# Slave1.net
KiCad netlist of a schematic drawn in Altium Designer
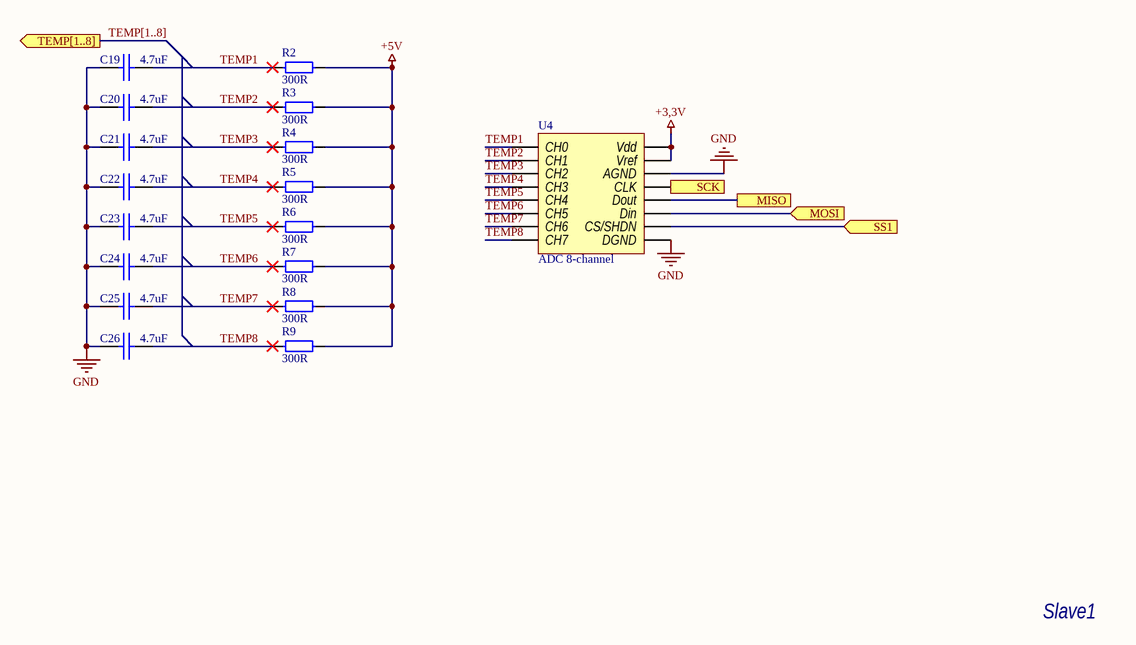
[diagram p0: Slave1.SchDoc]

(export (version "E")
  (design (tool "Eeschema 10.0.6"))
  (components
    (comp (ref "C19")
      (value "4.7uF")
      (footprint "0603 Capicator")
      (description "4.7uF X5R 25V 10% 0603")
      (fields
        (field (name "MANUFACTURER") "Murata Manufacturing")
        (field (name "PART NUMBER") "GRM188R61E475KE11D")
      )
      (libsource (lib "БУС") (part "Cap 4.7uF (0603)"))
    )
    (comp (ref "C20")
      (value "4.7uF")
      (footprint "0603 Capicator")
      (description "4.7uF X5R 25V 10% 0603")
      (fields
        (field (name "MANUFACTURER") "Murata Manufacturing")
        (field (name "PART NUMBER") "GRM188R61E475KE11D")
      )
      (libsource (lib "БУС") (part "Cap 4.7uF (0603)"))
    )
    (comp (ref "C21")
      (value "4.7uF")
      (footprint "0603 Capicator")
      (description "4.7uF X5R 25V 10% 0603")
      (fields
        (field (name "MANUFACTURER") "Murata Manufacturing")
        (field (name "PART NUMBER") "GRM188R61E475KE11D")
      )
      (libsource (lib "БУС") (part "Cap 4.7uF (0603)"))
    )
    (comp (ref "C22")
      (value "4.7uF")
      (footprint "0603 Capicator")
      (description "4.7uF X5R 25V 10% 0603")
      (fields
        (field (name "MANUFACTURER") "Murata Manufacturing")
        (field (name "PART NUMBER") "GRM188R61E475KE11D")
      )
      (libsource (lib "БУС") (part "Cap 4.7uF (0603)"))
    )
    (comp (ref "C23")
      (value "4.7uF")
      (footprint "0603 Capicator")
      (description "4.7uF X5R 25V 10% 0603")
      (fields
        (field (name "MANUFACTURER") "Murata Manufacturing")
        (field (name "PART NUMBER") "GRM188R61E475KE11D")
      )
      (libsource (lib "БУС") (part "Cap 4.7uF (0603)"))
    )
    (comp (ref "C24")
      (value "4.7uF")
      (footprint "0603 Capicator")
      (description "4.7uF X5R 25V 10% 0603")
      (fields
        (field (name "MANUFACTURER") "Murata Manufacturing")
        (field (name "PART NUMBER") "GRM188R61E475KE11D")
      )
      (libsource (lib "БУС") (part "Cap 4.7uF (0603)"))
    )
    (comp (ref "C25")
      (value "4.7uF")
      (footprint "0603 Capicator")
      (description "4.7uF X5R 25V 10% 0603")
      (fields
        (field (name "MANUFACTURER") "Murata Manufacturing")
        (field (name "PART NUMBER") "GRM188R61E475KE11D")
      )
      (libsource (lib "БУС") (part "Cap 4.7uF (0603)"))
    )
    (comp (ref "C26")
      (value "4.7uF")
      (footprint "0603 Capicator")
      (description "4.7uF X5R 25V 10% 0603")
      (fields
        (field (name "MANUFACTURER") "Murata Manufacturing")
        (field (name "PART NUMBER") "GRM188R61E475KE11D")
      )
      (libsource (lib "БУС") (part "Cap 4.7uF (0603)"))
    )
    (comp (ref "R2")
      (value "300R")
      (footprint "0603 Resistor")
      (description "0.1W 0603 300R, 1%")
      (fields (field (name "PART NUMBER") "RC0603FR-07360RL") (field (name "MANUFACTURER") "Taiwan"))
      (libsource (lib "БУС") (part "Res 300R (0603)"))
    )
    (comp (ref "R3")
      (value "300R")
      (footprint "0603 Resistor")
      (description "0.1W 0603 300R, 1%")
      (fields (field (name "PART NUMBER") "RC0603FR-07360RL") (field (name "MANUFACTURER") "Taiwan"))
      (libsource (lib "БУС") (part "Res 300R (0603)"))
    )
    (comp (ref "R4")
      (value "300R")
      (footprint "0603 Resistor")
      (description "0.1W 0603 300R, 1%")
      (fields (field (name "PART NUMBER") "RC0603FR-07360RL") (field (name "MANUFACTURER") "Taiwan"))
      (libsource (lib "БУС") (part "Res 300R (0603)"))
    )
    (comp (ref "R5")
      (value "300R")
      (footprint "0603 Resistor")
      (description "0.1W 0603 300R, 1%")
      (fields (field (name "PART NUMBER") "RC0603FR-07360RL") (field (name "MANUFACTURER") "Taiwan"))
      (libsource (lib "БУС") (part "Res 300R (0603)"))
    )
    (comp (ref "R6")
      (value "300R")
      (footprint "0603 Resistor")
      (description "0.1W 0603 300R, 1%")
      (fields (field (name "PART NUMBER") "RC0603FR-07360RL") (field (name "MANUFACTURER") "Taiwan"))
      (libsource (lib "БУС") (part "Res 300R (0603)"))
    )
    (comp (ref "R7")
      (value "300R")
      (footprint "0603 Resistor")
      (description "0.1W 0603 300R, 1%")
      (fields (field (name "PART NUMBER") "RC0603FR-07360RL") (field (name "MANUFACTURER") "Taiwan"))
      (libsource (lib "БУС") (part "Res 300R (0603)"))
    )
    (comp (ref "R8")
      (value "300R")
      (footprint "0603 Resistor")
      (description "0.1W 0603 300R, 1%")
      (fields (field (name "PART NUMBER") "RC0603FR-07360RL") (field (name "MANUFACTURER") "Taiwan"))
      (libsource (lib "БУС") (part "Res 300R (0603)"))
    )
    (comp (ref "R9")
      (value "300R")
      (footprint "0603 Resistor")
      (description "0.1W 0603 300R, 1%")
      (fields (field (name "PART NUMBER") "RC0603FR-07360RL") (field (name "MANUFACTURER") "Taiwan"))
      (libsource (lib "БУС") (part "Res 300R (0603)"))
    )
    (comp (ref "U4")
      (value "ADC 8-channel")
      (footprint "SOIC-16")
      (description "A/D converter with SPI serial interface")
      (fields (field (name "MANUFACTURER") "Microchip") (field (name "PART NUMBER") "MCP3008-I/SL"))
      (libsource (lib "БУС") (part "MCP3008-I/SL"))
    )
  )
  (nets
    (net (code "1") (name "+3,3V") (class "Default")
      (node (ref "U4") (pin "15") (pinfunction "Vref_15") (pintype "passive"))
      (node (ref "U4") (pin "16") (pinfunction "Vdd_16") (pintype "passive"))
    )
    (net (code "2") (name "+5V") (class "Default")
      (node (ref "R2") (pin "2") (pinfunction "2_2") (pintype "passive"))
      (node (ref "R3") (pin "2") (pinfunction "2_2") (pintype "passive"))
      (node (ref "R4") (pin "2") (pinfunction "2_2") (pintype "passive"))
      (node (ref "R5") (pin "2") (pinfunction "2_2") (pintype "passive"))
      (node (ref "R6") (pin "2") (pinfunction "2_2") (pintype "passive"))
      (node (ref "R7") (pin "2") (pinfunction "2_2") (pintype "passive"))
      (node (ref "R8") (pin "2") (pinfunction "2_2") (pintype "passive"))
      (node (ref "R9") (pin "2") (pinfunction "2_2") (pintype "passive"))
    )
    (net (code "3") (name "/MISO") (class "Default")
      (node (ref "U4") (pin "12") (pinfunction "Dout_12") (pintype "passive"))
    )
    (net (code "4") (name "/MOSI") (class "Default")
      (node (ref "U4") (pin "11") (pinfunction "Din_11") (pintype "passive"))
    )
    (net (code "5") (name "/SCK") (class "Default")
      (node (ref "U4") (pin "13") (pinfunction "CLK_13") (pintype "passive"))
    )
    (net (code "6") (name "/SS1") (class "Default")
      (node (ref "U4") (pin "10") (pinfunction "CS/SHDN_10") (pintype "passive"))
    )
    (net (code "7") (name "/TEMP1") (class "Default")
      (node (ref "C19") (pin "2") (pinfunction "2_2") (pintype "passive"))
      (node (ref "R2") (pin "1") (pinfunction "1_1") (pintype "passive"))
      (node (ref "U4") (pin "1") (pinfunction "CH0_1") (pintype "passive"))
    )
    (net (code "8") (name "/TEMP2") (class "Default")
      (node (ref "C20") (pin "2") (pinfunction "2_2") (pintype "passive"))
      (node (ref "R3") (pin "1") (pinfunction "1_1") (pintype "passive"))
      (node (ref "U4") (pin "2") (pinfunction "CH1_2") (pintype "passive"))
    )
    (net (code "9") (name "/TEMP3") (class "Default")
      (node (ref "C21") (pin "2") (pinfunction "2_2") (pintype "passive"))
      (node (ref "R4") (pin "1") (pinfunction "1_1") (pintype "passive"))
      (node (ref "U4") (pin "3") (pinfunction "CH2_3") (pintype "passive"))
    )
    (net (code "10") (name "/TEMP4") (class "Default")
      (node (ref "C22") (pin "2") (pinfunction "2_2") (pintype "passive"))
      (node (ref "R5") (pin "1") (pinfunction "1_1") (pintype "passive"))
      (node (ref "U4") (pin "4") (pinfunction "CH3_4") (pintype "passive"))
    )
    (net (code "11") (name "/TEMP5") (class "Default")
      (node (ref "C23") (pin "2") (pinfunction "2_2") (pintype "passive"))
      (node (ref "R6") (pin "1") (pinfunction "1_1") (pintype "passive"))
      (node (ref "U4") (pin "5") (pinfunction "CH4_5") (pintype "passive"))
    )
    (net (code "12") (name "/TEMP6") (class "Default")
      (node (ref "C24") (pin "2") (pinfunction "2_2") (pintype "passive"))
      (node (ref "R7") (pin "1") (pinfunction "1_1") (pintype "passive"))
      (node (ref "U4") (pin "6") (pinfunction "CH5_6") (pintype "passive"))
    )
    (net (code "13") (name "/TEMP7") (class "Default")
      (node (ref "C25") (pin "2") (pinfunction "2_2") (pintype "passive"))
      (node (ref "R8") (pin "1") (pinfunction "1_1") (pintype "passive"))
      (node (ref "U4") (pin "7") (pinfunction "CH6_7") (pintype "passive"))
    )
    (net (code "14") (name "/TEMP8") (class "Default")
      (node (ref "C26") (pin "2") (pinfunction "2_2") (pintype "passive"))
      (node (ref "R9") (pin "1") (pinfunction "1_1") (pintype "passive"))
      (node (ref "U4") (pin "8") (pinfunction "CH7_8") (pintype "passive"))
    )
    (net (code "16") (name "GND") (class "Default")
      (node (ref "C19") (pin "1") (pinfunction "1_1") (pintype "passive"))
      (node (ref "C20") (pin "1") (pinfunction "1_1") (pintype "passive"))
      (node (ref "C21") (pin "1") (pinfunction "1_1") (pintype "passive"))
      (node (ref "C22") (pin "1") (pinfunction "1_1") (pintype "passive"))
      (node (ref "C23") (pin "1") (pinfunction "1_1") (pintype "passive"))
      (node (ref "C24") (pin "1") (pinfunction "1_1") (pintype "passive"))
      (node (ref "C25") (pin "1") (pinfunction "1_1") (pintype "passive"))
      (node (ref "C26") (pin "1") (pinfunction "1_1") (pintype "passive"))
      (node (ref "U4") (pin "14") (pinfunction "AGND_14") (pintype "passive"))
      (node (ref "U4") (pin "9") (pinfunction "DGND_9") (pintype "passive"))
    )
  )
)
